# VoltageLevelMeter2.net
KiCad netlist of a schematic drawn in EAGLE
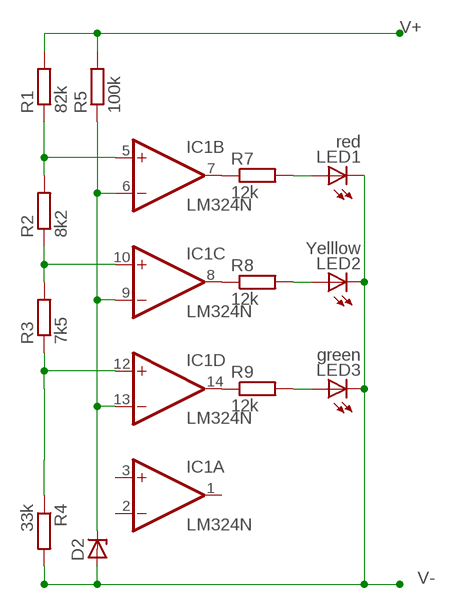
[diagram p0: schematic, sheet 1]

(export (version "E")
  (design (tool "Eeschema 10.0.6"))
  (components
    (comp (ref "D2")
      (value "ZENER-DIODEDO34-7")
      (footprint "eagle-import:DO34Z7")
      (libsource (lib "eagle-import") (part "ZENER-DIODEDO34-7"))
    )
    (comp (ref "IC1")
      (value "LM324N")
      (footprint "eagle-import:DIL14")
      (libsource (lib "eagle-import") (part "LM324N"))
    )
    (comp (ref "LED1")
      (value "red")
      (footprint "eagle-import:LED3MM")
      (libsource (lib "eagle-import") (part "LED3MM"))
    )
    (comp (ref "LED2")
      (value "Yelllow")
      (footprint "eagle-import:LED3MM")
      (libsource (lib "eagle-import") (part "LED3MM"))
    )
    (comp (ref "LED3")
      (value "green")
      (footprint "eagle-import:LED3MM")
      (libsource (lib "eagle-import") (part "LED3MM"))
    )
    (comp (ref "R1")
      (value "82k")
      (footprint "eagle-import:0207_7")
      (libsource (lib "eagle-import") (part "R-EU_0207/7"))
    )
    (comp (ref "R2")
      (value "8k2")
      (footprint "eagle-import:0207_7")
      (libsource (lib "eagle-import") (part "R-EU_0207/7"))
    )
    (comp (ref "R3")
      (value "7k5")
      (footprint "eagle-import:0207_7")
      (libsource (lib "eagle-import") (part "R-EU_0207/7"))
    )
    (comp (ref "R4")
      (value "33k")
      (footprint "eagle-import:0207_7")
      (libsource (lib "eagle-import") (part "R-EU_0207/7"))
    )
    (comp (ref "R5")
      (value "100k")
      (footprint "eagle-import:0207_7")
      (libsource (lib "eagle-import") (part "R-EU_0207/7"))
    )
    (comp (ref "R7")
      (value "12k")
      (footprint "eagle-import:0207_7")
      (libsource (lib "eagle-import") (part "R-EU_0207/7"))
    )
    (comp (ref "R8")
      (value "12k")
      (footprint "eagle-import:0207_7")
      (libsource (lib "eagle-import") (part "R-EU_0207/7"))
    )
    (comp (ref "R9")
      (value "12k")
      (footprint "eagle-import:0207_7")
      (libsource (lib "eagle-import") (part "R-EU_0207/7"))
    )
  )
  (nets
    (net (code "1") (name "/V+") (class "Default")
      (node (ref "R1") (pin "2") (pinfunction "2_2") (pintype "passive"))
      (node (ref "R5") (pin "2") (pinfunction "2_2") (pintype "passive"))
    )
    (net (code "2") (name "/V-") (class "Default")
      (node (ref "D2") (pin "A") (pinfunction "A_A") (pintype "passive"))
      (node (ref "LED1") (pin "K") (pinfunction "C_K") (pintype "passive"))
      (node (ref "LED2") (pin "K") (pinfunction "C_K") (pintype "passive"))
      (node (ref "LED3") (pin "K") (pinfunction "C_K") (pintype "passive"))
      (node (ref "R4") (pin "2") (pinfunction "2_2") (pintype "passive"))
    )
    (net (code "3") (name "Net-(IC1B-+IN)") (class "Default")
      (node (ref "IC1") (pin "5") (pinfunction "+IN_5") (pintype "input"))
      (node (ref "R1") (pin "1") (pinfunction "1_1") (pintype "passive"))
      (node (ref "R2") (pin "2") (pinfunction "2_2") (pintype "passive"))
    )
    (net (code "4") (name "Net-(IC1B--IN)") (class "Default")
      (node (ref "D2") (pin "C") (pinfunction "C_C") (pintype "passive"))
      (node (ref "IC1") (pin "13") (pinfunction "-IN_13") (pintype "input"))
      (node (ref "IC1") (pin "6") (pinfunction "-IN_6") (pintype "input"))
      (node (ref "IC1") (pin "9") (pinfunction "-IN_9") (pintype "input"))
      (node (ref "R5") (pin "1") (pinfunction "1_1") (pintype "passive"))
    )
    (net (code "5") (name "Net-(IC1B-OUT)") (class "Default")
      (node (ref "IC1") (pin "7") (pinfunction "OUT_7") (pintype "output"))
      (node (ref "R7") (pin "1") (pinfunction "1_1") (pintype "passive"))
    )
    (net (code "6") (name "Net-(IC1C-+IN)") (class "Default")
      (node (ref "IC1") (pin "10") (pinfunction "+IN_10") (pintype "input"))
      (node (ref "R2") (pin "1") (pinfunction "1_1") (pintype "passive"))
      (node (ref "R3") (pin "2") (pinfunction "2_2") (pintype "passive"))
    )
    (net (code "7") (name "Net-(IC1C-OUT)") (class "Default")
      (node (ref "IC1") (pin "8") (pinfunction "OUT_8") (pintype "output"))
      (node (ref "R8") (pin "1") (pinfunction "1_1") (pintype "passive"))
    )
    (net (code "8") (name "Net-(IC1D-+IN)") (class "Default")
      (node (ref "IC1") (pin "12") (pinfunction "+IN_12") (pintype "input"))
      (node (ref "R3") (pin "1") (pinfunction "1_1") (pintype "passive"))
      (node (ref "R4") (pin "1") (pinfunction "1_1") (pintype "passive"))
    )
    (net (code "9") (name "Net-(IC1D-OUT)") (class "Default")
      (node (ref "IC1") (pin "14") (pinfunction "OUT_14") (pintype "output"))
      (node (ref "R9") (pin "1") (pinfunction "1_1") (pintype "passive"))
    )
    (net (code "10") (name "Net-(LED1-PadA)") (class "Default")
      (node (ref "LED1") (pin "A") (pinfunction "A_A") (pintype "passive"))
      (node (ref "R7") (pin "2") (pinfunction "2_2") (pintype "passive"))
    )
    (net (code "11") (name "Net-(LED2-PadA)") (class "Default")
      (node (ref "LED2") (pin "A") (pinfunction "A_A") (pintype "passive"))
      (node (ref "R8") (pin "2") (pinfunction "2_2") (pintype "passive"))
    )
    (net (code "12") (name "Net-(LED3-PadA)") (class "Default")
      (node (ref "LED3") (pin "A") (pinfunction "A_A") (pintype "passive"))
      (node (ref "R9") (pin "2") (pinfunction "2_2") (pintype "passive"))
    )
    (net (code "13") (name "unconnected-(IC1A-+IN-Pad3)") (class "Default")
      (node (ref "IC1") (pin "3") (pinfunction "+IN_3") (pintype "input"))
    )
    (net (code "14") (name "unconnected-(IC1A--IN-Pad2)") (class "Default")
      (node (ref "IC1") (pin "2") (pinfunction "-IN_2") (pintype "input"))
    )
    (net (code "15") (name "unconnected-(IC1A-OUT-Pad1)") (class "Default")
      (node (ref "IC1") (pin "1") (pinfunction "OUT_1") (pintype "output"))
    )
  )
)
